# Adafruit_128x64_Mono_OLED_PCB_v2.net
KiCad netlist of a schematic drawn in Altium Designer
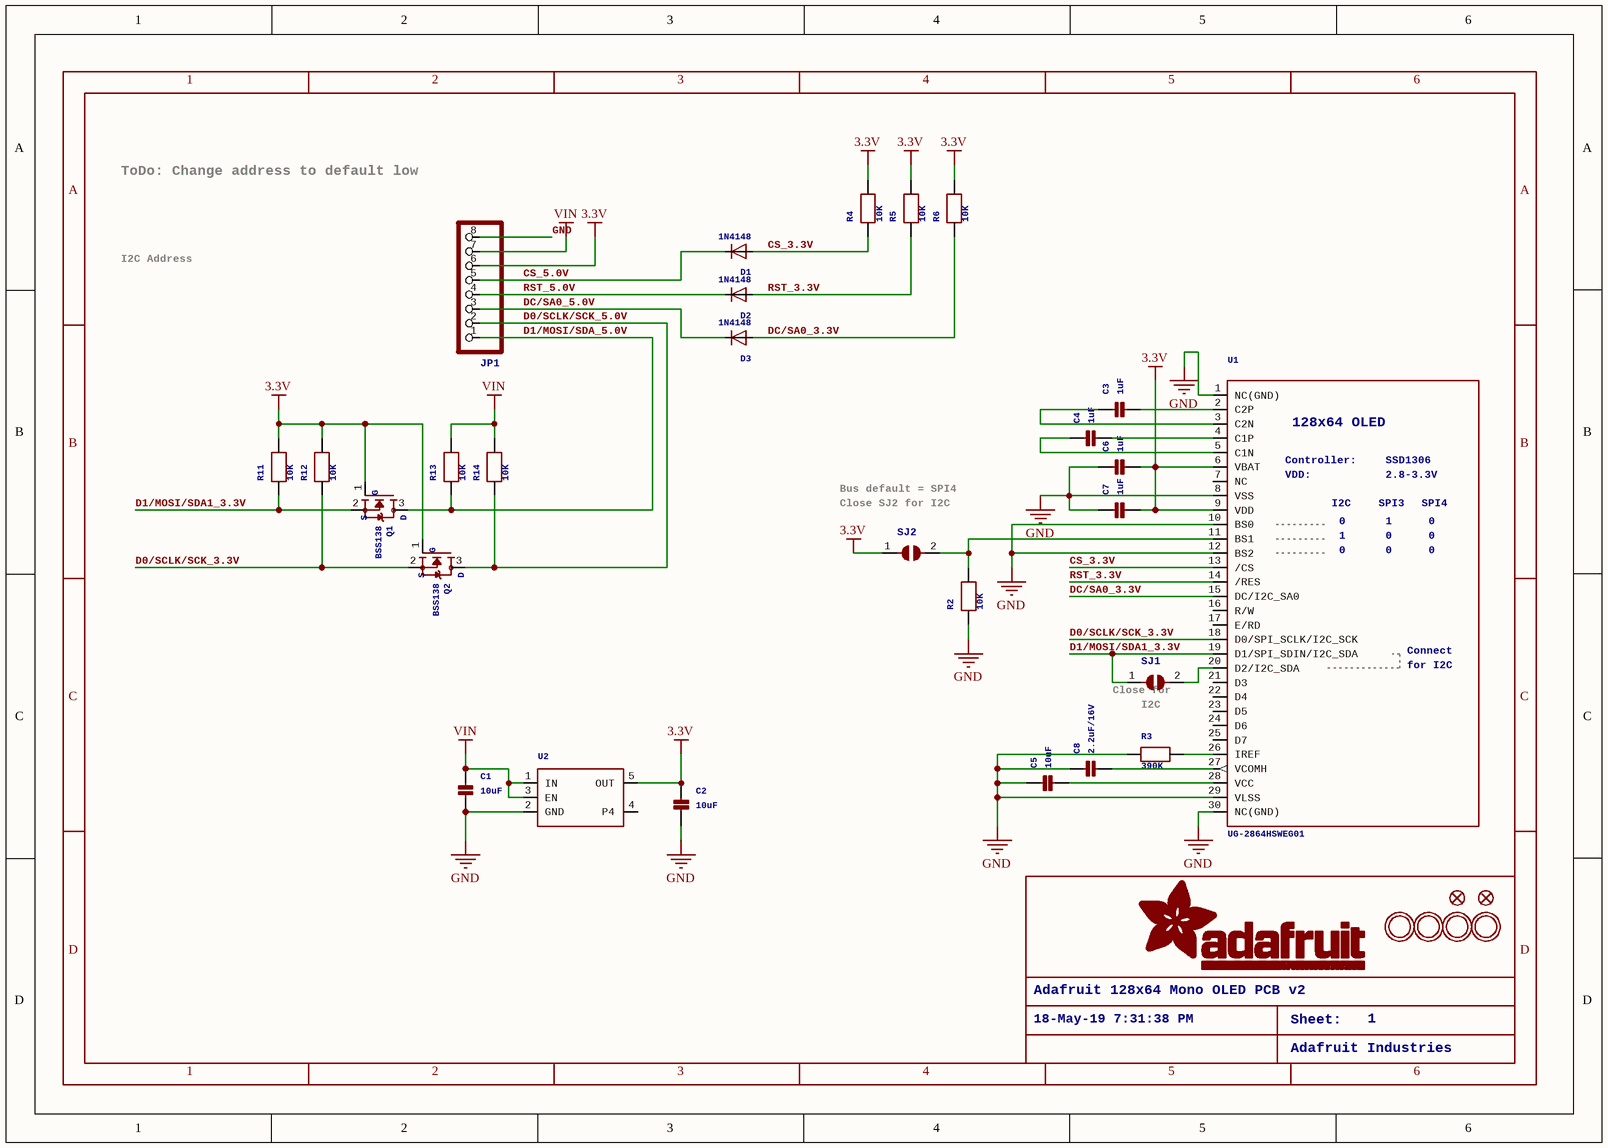
[diagram p0: Adafruit 128x64 Mono OLED PCB v2.SchDoc]

(export (version "E")
  (design (tool "Eeschema 10.0.6"))
  (components
    (comp (ref "C1") (value "10uF") (footprint "0805") (libsource (lib "") (part "CAP_CERAMIC0805_1")))
    (comp (ref "C2") (value "10uF") (footprint "0805") (libsource (lib "") (part "CAP_CERAMIC0805_1")))
    (comp (ref "C3")
      (value "1uF")
      (footprint "0805")
      (libsource (lib "microbuilder") (part "CAP_CERAMIC0805"))
    )
    (comp (ref "C4")
      (value "1uF")
      (footprint "0805")
      (libsource (lib "microbuilder") (part "CAP_CERAMIC0805"))
    )
    (comp (ref "C5")
      (value "10uF")
      (footprint "0805")
      (libsource (lib "microbuilder") (part "CAP_CERAMIC0805"))
    )
    (comp (ref "C6")
      (value "1uF")
      (footprint "0805")
      (libsource (lib "microbuilder") (part "CAP_CERAMIC0805"))
    )
    (comp (ref "C7")
      (value "1uF")
      (footprint "0805")
      (libsource (lib "microbuilder") (part "CAP_CERAMIC0805"))
    )
    (comp (ref "C8")
      (value "2.2uF/16V")
      (footprint "0805")
      (libsource (lib "microbuilder") (part "CAP_CERAMIC0805"))
    )
    (comp (ref "D1")
      (value "1N4148")
      (footprint "SOD-323")
      (libsource (lib "microbuilder") (part "DIODESOD-323"))
    )
    (comp (ref "D2")
      (value "1N4148")
      (footprint "SOD-323")
      (libsource (lib "microbuilder") (part "DIODESOD-323"))
    )
    (comp (ref "D3")
      (value "1N4148")
      (footprint "SOD-323")
      (libsource (lib "microbuilder") (part "DIODESOD-323"))
    )
    (comp (ref "FID1")
      (value "FIDUCIAL\"\"")
      (footprint "FIDUCIAL_1MM")
      (description "Fiducial Alignment PointsVarious fiducial points for machine vision alignment.")
      (libsource (lib "microbuilder") (part "FIDUCIAL{dblquote}{dblquote}"))
    )
    (comp (ref "FID2")
      (value "FIDUCIAL\"\"")
      (footprint "FIDUCIAL_1MM")
      (description "Fiducial Alignment PointsVarious fiducial points for machine vision alignment.")
      (libsource (lib "microbuilder") (part "FIDUCIAL{dblquote}{dblquote}"))
    )
    (comp (ref "JP1")
      (value "HEADER-1X870MIL")
      (footprint "1X08_ROUND_70")
      (description "PIN HEADER")
      (libsource (lib "microbuilder") (part "HEADER-1X870MIL"))
    )
    (comp (ref "Q1")
      (value "BSS138")
      (footprint "SOT23-WIDE")
      (fields (field (name "D") "D") (field (name "S") "S") (field (name "G") "G"))
      (libsource (lib "microbuilder") (part "MOSFET-NWIDE"))
    )
    (comp (ref "Q2")
      (value "BSS138")
      (footprint "SOT23-WIDE")
      (fields (field (name "D") "D") (field (name "S") "S") (field (name "G") "G"))
      (libsource (lib "microbuilder") (part "MOSFET-NWIDE"))
    )
    (comp (ref "R2") (value "10K") (footprint "0805") (libsource (lib "microbuilder") (part "RESISTOR0805")))
    (comp (ref "R3") (value "390K") (footprint "0805") (libsource (lib "microbuilder") (part "RESISTOR0805")))
    (comp (ref "R4") (value "10K") (footprint "0805") (libsource (lib "microbuilder") (part "RESISTOR0805")))
    (comp (ref "R5") (value "10K") (footprint "0805") (libsource (lib "microbuilder") (part "RESISTOR0805")))
    (comp (ref "R6") (value "10K") (footprint "0805") (libsource (lib "microbuilder") (part "RESISTOR0805")))
    (comp (ref "R11") (value "10K") (footprint "0805") (libsource (lib "microbuilder") (part "RESISTOR0805")))
    (comp (ref "R12") (value "10K") (footprint "0805") (libsource (lib "microbuilder") (part "RESISTOR0805")))
    (comp (ref "R13") (value "10K") (footprint "0805") (libsource (lib "microbuilder") (part "RESISTOR0805")))
    (comp (ref "R14") (value "10K") (footprint "0805") (libsource (lib "microbuilder") (part "RESISTOR0805")))
    (comp (ref "SJ1")
      (value "SOLDERJUMPERREFLOW_NOPASTE")
      (footprint "SOLDERJUMPER_REFLOW_NOPASTE")
      (libsource (lib "microbuilder") (part "SOLDERJUMPERREFLOW_NOPASTE"))
    )
    (comp (ref "SJ2")
      (value "SOLDERJUMPERREFLOW_NOPASTE")
      (footprint "SOLDERJUMPER_REFLOW_NOPASTE")
      (libsource (lib "microbuilder") (part "SOLDERJUMPERREFLOW_NOPASTE"))
    )
    (comp (ref "U$23")
      (value "MOUNTINGHOLE2.5")
      (footprint "MOUNTINGHOLE_2.5_PLATED")
      (description "Mounting HoleFor #2 screws (0.086\"/2.18mm width, 0.094\"/2.4mm hole) use 2.5mm")
      (libsource (lib "microbuilder") (part "MOUNTINGHOLE2.5"))
    )
    (comp (ref "U$24")
      (value "MOUNTINGHOLE2.5")
      (footprint "MOUNTINGHOLE_2.5_PLATED")
      (description "Mounting HoleFor #2 screws (0.086\"/2.18mm width, 0.094\"/2.4mm hole) use 2.5mm")
      (libsource (lib "microbuilder") (part "MOUNTINGHOLE2.5"))
    )
    (comp (ref "U$25")
      (value "MOUNTINGHOLE2.5")
      (footprint "MOUNTINGHOLE_2.5_PLATED")
      (description "Mounting HoleFor #2 screws (0.086\"/2.18mm width, 0.094\"/2.4mm hole) use 2.5mm")
      (libsource (lib "microbuilder") (part "MOUNTINGHOLE2.5"))
    )
    (comp (ref "U$26")
      (value "MOUNTINGHOLE2.5")
      (footprint "MOUNTINGHOLE_2.5_PLATED")
      (description "Mounting HoleFor #2 screws (0.086\"/2.18mm width, 0.094\"/2.4mm hole) use 2.5mm")
      (libsource (lib "microbuilder") (part "MOUNTINGHOLE2.5"))
    )
    (comp (ref "U1")
      (value "UG-2864HSWEG01")
      (footprint "UG-2864HSWEG01_0.96IN_WRAPAROUND")
      (fields
        (field (name "128X64OLED") "128x64 OLED")
        (field (name "I2C") "I2C")
        (field (name "SPI3") "SPI3")
        (field (name "0") "0")
        (field (name "0_1") "0")
        (field (name "0_2") "0")
        (field (name "0_3") "0")
        (field (name "1") "1")
        (field (name "1_1") "1")
        (field (name "CONNECT") "Connect")
        (field (name "FORI2C") "for I2C")
        (field (name "CONTROLLER") "Controller:")
        (field (name "SSD1306") "SSD1306")
        (field (name "VDD") "VDD:")
        (field (name "2.8-3.3V") "2.8-3.3V")
        (field (name "SPI4") "SPI4")
        (field (name "0_4") "0")
        (field (name "0_5") "0")
        (field (name "0_6") "0")
      )
      (libsource (lib "microbuilder") (part "DISP_OLED_UG-2864HSWEG010.96{dblquote}"))
    )
    (comp (ref "U2")
      (value "VREG_SOT23-5")
      (footprint "SOT23-5")
      (libsource (lib "microbuilder") (part "VREG_SOT23-5"))
    )
  )
  (nets
    (net (code "1") (name "/CS_3.3V") (class "Default")
      (node (ref "D1") (pin "A") (pinfunction "A_A") (pintype "passive"))
      (node (ref "R4") (pin "1") (pinfunction "1_1") (pintype "passive"))
      (node (ref "U1") (pin "13") (pinfunction "/CS_13") (pintype "passive"))
    )
    (net (code "2") (name "/CS_5.0V") (class "Default")
      (node (ref "D1") (pin "C") (pinfunction "C_C") (pintype "passive"))
      (node (ref "JP1") (pin "5") (pinfunction "5_5") (pintype "passive"))
    )
    (net (code "3") (name "/D0{slash}SCLK{slash}SCK_3.3V") (class "Default")
      (node (ref "Q2") (pin "2") (pinfunction "S_2") (pintype "passive"))
      (node (ref "R12") (pin "1") (pinfunction "1_1") (pintype "passive"))
      (node (ref "U1") (pin "18") (pinfunction "D0/SPI_SCLK/I2C_SCK_18") (pintype "passive"))
    )
    (net (code "4") (name "/D0{slash}SCLK{slash}SCK_5.0V") (class "Default")
      (node (ref "JP1") (pin "2") (pinfunction "2_2") (pintype "passive"))
      (node (ref "Q2") (pin "3") (pinfunction "D_3") (pintype "passive"))
      (node (ref "R14") (pin "1") (pinfunction "1_1") (pintype "passive"))
    )
    (net (code "5") (name "/D1{slash}MOSI{slash}SDA1_3.3V") (class "Default")
      (node (ref "Q1") (pin "2") (pinfunction "S_2") (pintype "passive"))
      (node (ref "R11") (pin "1") (pinfunction "1_1") (pintype "passive"))
      (node (ref "SJ1") (pin "1") (pinfunction "1_1") (pintype "passive"))
      (node (ref "U1") (pin "19") (pinfunction "D1/SPI_SDIN/I2C_SDA_19") (pintype "passive"))
    )
    (net (code "6") (name "/D1{slash}MOSI{slash}SDA_5.0V") (class "Default")
      (node (ref "JP1") (pin "1") (pinfunction "1_1") (pintype "passive"))
      (node (ref "Q1") (pin "3") (pinfunction "D_3") (pintype "passive"))
      (node (ref "R13") (pin "1") (pinfunction "1_1") (pintype "passive"))
    )
    (net (code "7") (name "/DC{slash}SA0_3.3V") (class "Default")
      (node (ref "D3") (pin "A") (pinfunction "A_A") (pintype "passive"))
      (node (ref "R6") (pin "1") (pinfunction "1_1") (pintype "passive"))
      (node (ref "U1") (pin "15") (pinfunction "DC/I2C_SA0_15") (pintype "passive"))
    )
    (net (code "8") (name "/DC{slash}SA0_5.0V") (class "Default")
      (node (ref "D3") (pin "C") (pinfunction "C_C") (pintype "passive"))
      (node (ref "JP1") (pin "3") (pinfunction "3_3") (pintype "passive"))
    )
    (net (code "9") (name "/RST_3.3V") (class "Default")
      (node (ref "D2") (pin "A") (pinfunction "A_A") (pintype "passive"))
      (node (ref "R5") (pin "1") (pinfunction "1_1") (pintype "passive"))
      (node (ref "U1") (pin "14") (pinfunction "/RES_14") (pintype "passive"))
    )
    (net (code "10") (name "/RST_5.0V") (class "Default")
      (node (ref "D2") (pin "C") (pinfunction "C_C") (pintype "passive"))
      (node (ref "JP1") (pin "4") (pinfunction "4_4") (pintype "passive"))
    )
    (net (code "11") (name "3.3V") (class "Default")
      (node (ref "C2") (pin "1") (pinfunction "P$1_1") (pintype "passive"))
      (node (ref "C6") (pin "2") (pinfunction "P$2_2") (pintype "passive"))
      (node (ref "C7") (pin "2") (pinfunction "P$2_2") (pintype "passive"))
      (node (ref "JP1") (pin "6") (pinfunction "6_6") (pintype "passive"))
      (node (ref "Q1") (pin "1") (pinfunction "G_1") (pintype "passive"))
      (node (ref "Q2") (pin "1") (pinfunction "G_1") (pintype "passive"))
      (node (ref "R11") (pin "2") (pinfunction "2_2") (pintype "passive"))
      (node (ref "R12") (pin "2") (pinfunction "2_2") (pintype "passive"))
      (node (ref "R4") (pin "2") (pinfunction "2_2") (pintype "passive"))
      (node (ref "R5") (pin "2") (pinfunction "2_2") (pintype "passive"))
      (node (ref "R6") (pin "2") (pinfunction "2_2") (pintype "passive"))
      (node (ref "SJ2") (pin "1") (pinfunction "1_1") (pintype "passive"))
      (node (ref "U1") (pin "6") (pinfunction "VBAT_6") (pintype "passive"))
      (node (ref "U1") (pin "9") (pinfunction "VDD_9") (pintype "power_in"))
      (node (ref "U2") (pin "5") (pinfunction "OUT_5") (pintype "passive"))
    )
    (net (code "12") (name "GND") (class "Default")
      (node (ref "C1") (pin "2") (pinfunction "P$2_2") (pintype "passive"))
      (node (ref "C2") (pin "2") (pinfunction "P$2_2") (pintype "passive"))
      (node (ref "C5") (pin "1") (pinfunction "P$1_1") (pintype "passive"))
      (node (ref "C6") (pin "1") (pinfunction "P$1_1") (pintype "passive"))
      (node (ref "C7") (pin "1") (pinfunction "P$1_1") (pintype "passive"))
      (node (ref "C8") (pin "1") (pinfunction "P$1_1") (pintype "passive"))
      (node (ref "JP1") (pin "8") (pinfunction "8_8") (pintype "passive"))
      (node (ref "R2") (pin "1") (pinfunction "1_1") (pintype "passive"))
      (node (ref "R3") (pin "1") (pinfunction "1_1") (pintype "passive"))
      (node (ref "U1") (pin "1") (pinfunction "NC(GND)_1") (pintype "passive"))
      (node (ref "U1") (pin "10") (pinfunction "BS0_10") (pintype "passive"))
      (node (ref "U1") (pin "12") (pinfunction "BS2_12") (pintype "passive"))
      (node (ref "U1") (pin "29") (pinfunction "VLSS_29") (pintype "power_in"))
      (node (ref "U1") (pin "30") (pinfunction "NC(GND)_30") (pintype "passive"))
      (node (ref "U1") (pin "8") (pinfunction "VSS_8") (pintype "power_in"))
      (node (ref "U2") (pin "2") (pinfunction "GND_2") (pintype "passive"))
    )
    (net (code "13") (name "Net-(C3-P$1)") (class "Default")
      (node (ref "C3") (pin "1") (pinfunction "P$1_1") (pintype "passive"))
      (node (ref "U1") (pin "3") (pinfunction "C2N_3") (pintype "passive"))
    )
    (net (code "14") (name "Net-(C3-P$2)") (class "Default")
      (node (ref "C3") (pin "2") (pinfunction "P$2_2") (pintype "passive"))
      (node (ref "U1") (pin "2") (pinfunction "C2P_2") (pintype "passive"))
    )
    (net (code "15") (name "Net-(C4-P$1)") (class "Default")
      (node (ref "C4") (pin "1") (pinfunction "P$1_1") (pintype "passive"))
      (node (ref "U1") (pin "5") (pinfunction "C1N_5") (pintype "passive"))
    )
    (net (code "16") (name "Net-(C4-P$2)") (class "Default")
      (node (ref "C4") (pin "2") (pinfunction "P$2_2") (pintype "passive"))
      (node (ref "U1") (pin "4") (pinfunction "C1P_4") (pintype "passive"))
    )
    (net (code "17") (name "Net-(C5-P$2)") (class "Default")
      (node (ref "C5") (pin "2") (pinfunction "P$2_2") (pintype "passive"))
      (node (ref "U1") (pin "28") (pinfunction "VCC_28") (pintype "power_in"))
    )
    (net (code "18") (name "Net-(C8-P$2)") (class "Default")
      (node (ref "C8") (pin "2") (pinfunction "P$2_2") (pintype "passive"))
      (node (ref "U1") (pin "27") (pinfunction "VCOMH_27") (pintype "output"))
    )
    (net (code "19") (name "Net-(U1-BS1)") (class "Default")
      (node (ref "R2") (pin "2") (pinfunction "2_2") (pintype "passive"))
      (node (ref "SJ2") (pin "2") (pinfunction "2_2") (pintype "passive"))
      (node (ref "U1") (pin "11") (pinfunction "BS1_11") (pintype "passive"))
    )
    (net (code "20") (name "Net-(U1-D2{slash}I2C_SDA)") (class "Default")
      (node (ref "SJ1") (pin "2") (pinfunction "2_2") (pintype "passive"))
      (node (ref "U1") (pin "20") (pinfunction "D2/I2C_SDA_20") (pintype "passive"))
    )
    (net (code "21") (name "Net-(U1-IREF)") (class "Default")
      (node (ref "R3") (pin "2") (pinfunction "2_2") (pintype "passive"))
      (node (ref "U1") (pin "26") (pinfunction "IREF_26") (pintype "passive"))
    )
    (net (code "22") (name "VIN") (class "Default")
      (node (ref "C1") (pin "1") (pinfunction "P$1_1") (pintype "passive"))
      (node (ref "JP1") (pin "7") (pinfunction "7_7") (pintype "passive"))
      (node (ref "R13") (pin "2") (pinfunction "2_2") (pintype "passive"))
      (node (ref "R14") (pin "2") (pinfunction "2_2") (pintype "passive"))
      (node (ref "U2") (pin "1") (pinfunction "IN_1") (pintype "passive"))
      (node (ref "U2") (pin "3") (pinfunction "EN_3") (pintype "passive"))
    )
    (net (code "23") (name "unconnected-(U1-D3-Pad21)") (class "Default")
      (node (ref "U1") (pin "21") (pinfunction "D3_21") (pintype "passive"))
    )
    (net (code "24") (name "unconnected-(U1-D4-Pad22)") (class "Default")
      (node (ref "U1") (pin "22") (pinfunction "D4_22") (pintype "passive"))
    )
    (net (code "25") (name "unconnected-(U1-D5-Pad23)") (class "Default")
      (node (ref "U1") (pin "23") (pinfunction "D5_23") (pintype "passive"))
    )
    (net (code "26") (name "unconnected-(U1-D6-Pad24)") (class "Default")
      (node (ref "U1") (pin "24") (pinfunction "D6_24") (pintype "passive"))
    )
    (net (code "27") (name "unconnected-(U1-D7-Pad25)") (class "Default")
      (node (ref "U1") (pin "25") (pinfunction "D7_25") (pintype "passive"))
    )
    (net (code "28") (name "unconnected-(U1-E{slash}RD-Pad17)") (class "Default")
      (node (ref "U1") (pin "17") (pinfunction "E/RD_17") (pintype "passive"))
    )
    (net (code "29") (name "unconnected-(U1-NC-Pad7)") (class "Default")
      (node (ref "U1") (pin "7") (pinfunction "NC_7") (pintype "passive"))
    )
    (net (code "30") (name "unconnected-(U1-R{slash}W-Pad16)") (class "Default")
      (node (ref "U1") (pin "16") (pinfunction "R/W_16") (pintype "passive"))
    )
    (net (code "31") (name "unconnected-(U2-P4-Pad4)") (class "Default")
      (node (ref "U2") (pin "4") (pinfunction "P4_4") (pintype "passive"))
    )
  )
)
